# csxcad.net
KiCad netlist of a schematic drawn in EAGLE
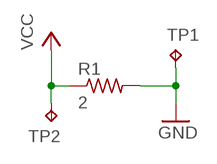
[diagram p0: schematic, sheet 1]

(export (version "E")
  (design (tool "Eeschema 10.0.6"))
  (components
    (comp (ref "R1")
      (value "2")
      (footprint "eagle-import:R0603")
      (libsource (lib "eagle-import") (part "R-US_R0603"))
    )
    (comp (ref "TP1")
      (value "TPB2,54")
      (footprint "eagle-import:B2,54")
      (libsource (lib "eagle-import") (part "TPB2,54"))
    )
    (comp (ref "TP2")
      (value "TPB2,54")
      (footprint "eagle-import:B2,54")
      (libsource (lib "eagle-import") (part "TPB2,54"))
    )
  )
  (nets
    (net (code "1") (name "GND") (class "Default")
      (node (ref "R1") (pin "2") (pinfunction "2_2") (pintype "passive"))
      (node (ref "TP1") (pin "TP") (pinfunction "TP_TP") (pintype "input"))
    )
    (net (code "2") (name "VCC") (class "Default")
      (node (ref "R1") (pin "1") (pinfunction "1_1") (pintype "passive"))
      (node (ref "TP2") (pin "TP") (pinfunction "TP_TP") (pintype "input"))
    )
  )
)
